# IDC-RJ45_connector_v1.net
KiCad netlist of a schematic drawn in EAGLE
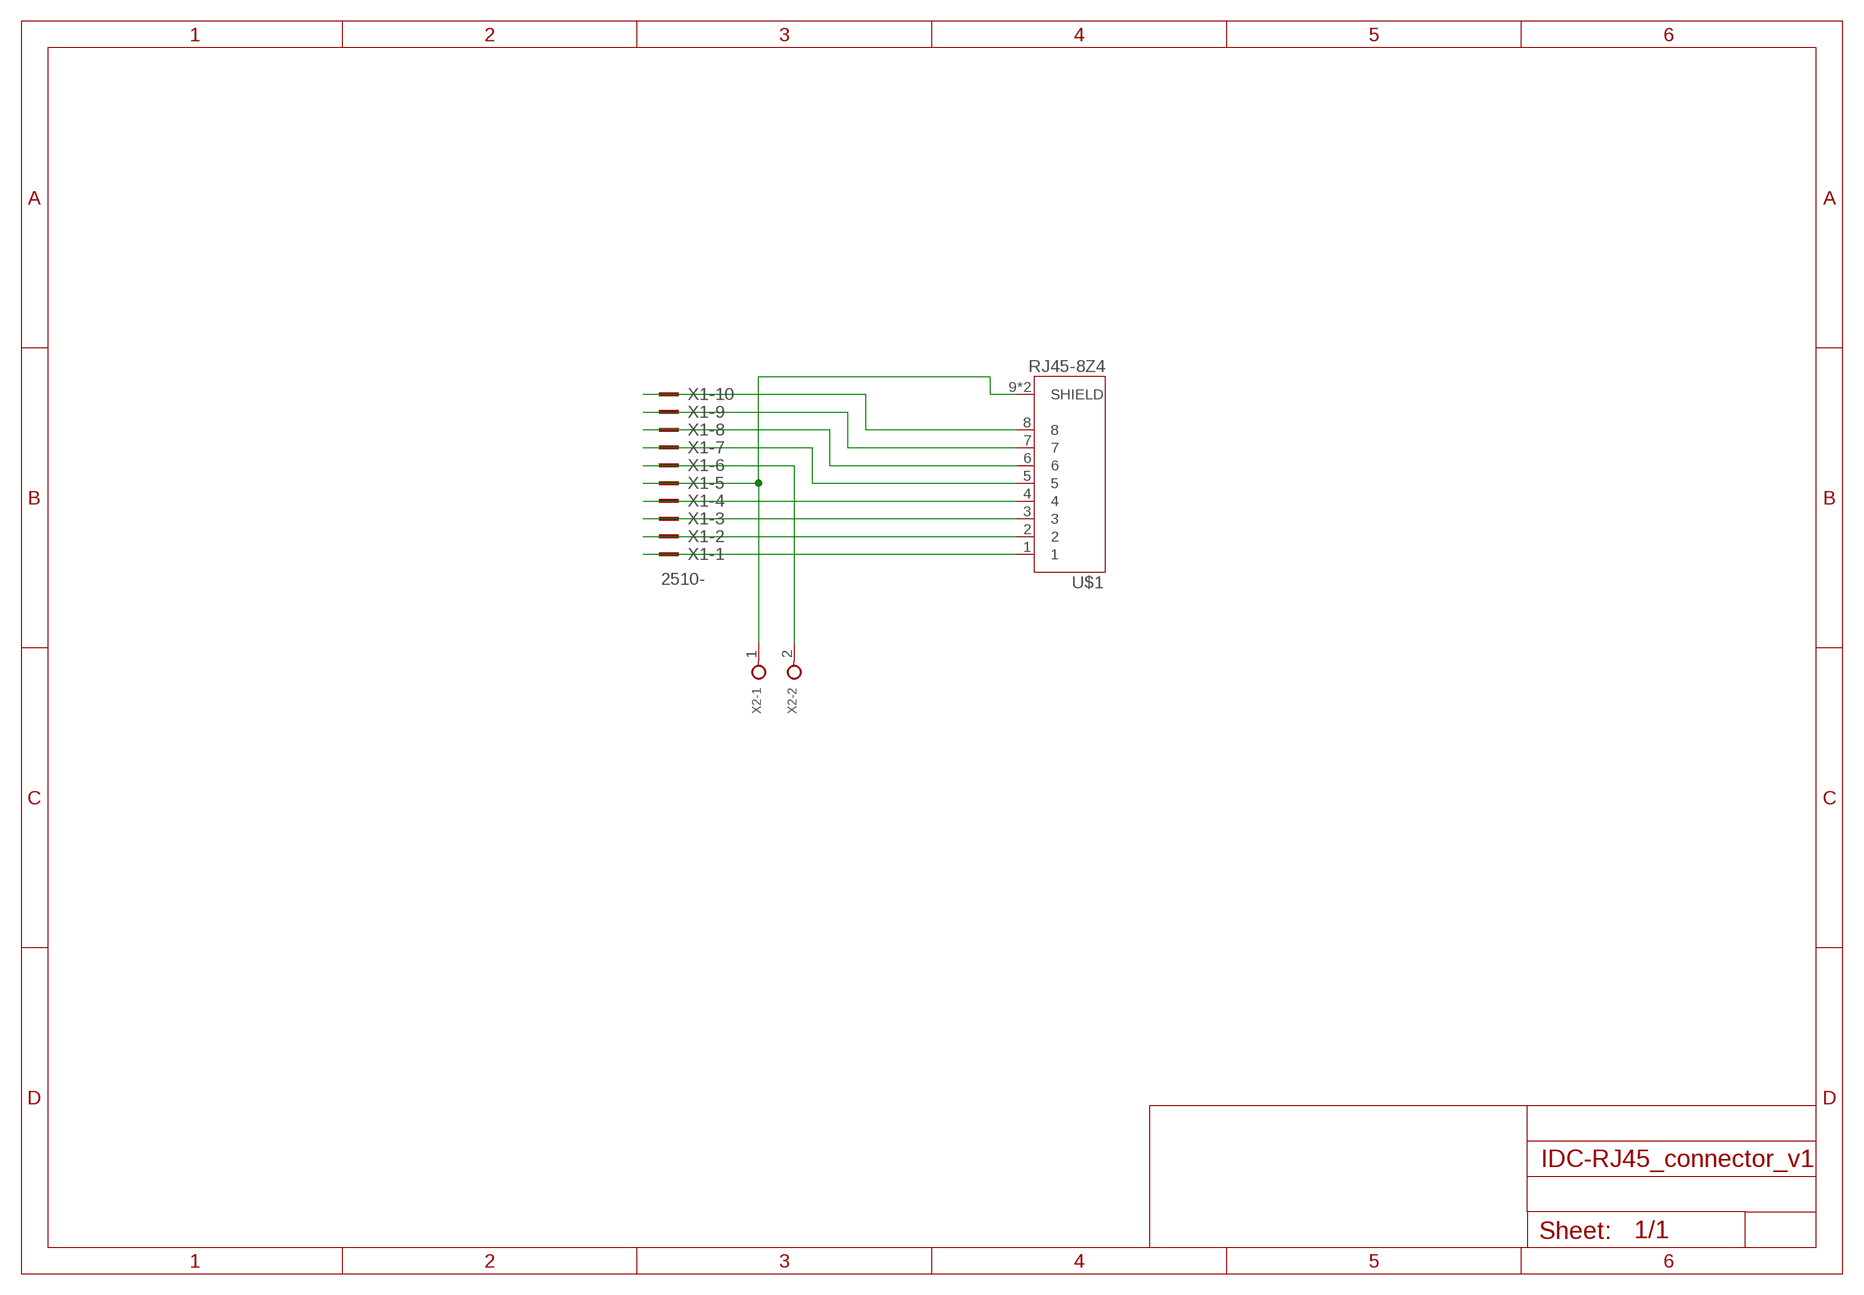
[diagram p0: schematic, sheet 1]

(export (version "E")
  (design (tool "Eeschema 10.0.6"))
  (components
    (comp (ref "U$1")
      (value "RJ45-8Z4")
      (footprint "eagle-import:TE_RJ45-8Z4")
      (fields (field (name "MF") "TE Connectivity"))
      (libsource (lib "eagle-import") (part "RJ45-8Z4"))
    )
    (comp (ref "X1")
      (value "2510-")
      (footprint "eagle-import:PAK100_2500-10")
      (fields (field (name "MF") "3M") (field (name "MPN") "2510-6002UB"))
      (libsource (lib "eagle-import") (part "2510-"))
    )
    (comp (ref "X2")
      (value "TERMINAL-5MM-2POLE")
      (footprint "eagle-import:TERMINAL_2P_5MM")
      (libsource (lib "eagle-import") (part "TERMINAL-5MM-2POLE"))
    )
  )
  (nets
    (net (code "1") (name "Net-(X1A-KL)") (class "Default")
      (node (ref "U$1") (pin "1") (pinfunction "1_1") (pintype "passive"))
      (node (ref "X1") (pin "1") (pinfunction "KL_1") (pintype "passive"))
    )
    (net (code "2") (name "Net-(X1B-KL)") (class "Default")
      (node (ref "U$1") (pin "8") (pinfunction "8_8") (pintype "passive"))
      (node (ref "X1") (pin "10") (pinfunction "KL_10") (pintype "passive"))
    )
    (net (code "3") (name "Net-(X1C-KL)") (class "Default")
      (node (ref "U$1") (pin "2") (pinfunction "2_2") (pintype "passive"))
      (node (ref "X1") (pin "2") (pinfunction "KL_2") (pintype "passive"))
    )
    (net (code "4") (name "Net-(X1D-KL)") (class "Default")
      (node (ref "U$1") (pin "3") (pinfunction "3_3") (pintype "passive"))
      (node (ref "X1") (pin "3") (pinfunction "KL_3") (pintype "passive"))
    )
    (net (code "5") (name "Net-(X1E-KL)") (class "Default")
      (node (ref "U$1") (pin "4") (pinfunction "4_4") (pintype "passive"))
      (node (ref "X1") (pin "4") (pinfunction "KL_4") (pintype "passive"))
    )
    (net (code "6") (name "Net-(X1F-KL)") (class "Default")
      (node (ref "U$1") (pin "10") (pinfunction "SHIELD_10") (pintype "passive"))
      (node (ref "U$1") (pin "9") (pinfunction "SHIELD_9") (pintype "passive"))
      (node (ref "X1") (pin "5") (pinfunction "KL_5") (pintype "passive"))
      (node (ref "X2") (pin "1") (pinfunction "P$1_1") (pintype "passive"))
    )
    (net (code "7") (name "Net-(X1G-KL)") (class "Default")
      (node (ref "X1") (pin "6") (pinfunction "KL_6") (pintype "passive"))
      (node (ref "X2") (pin "2") (pinfunction "P$2_2") (pintype "passive"))
    )
    (net (code "8") (name "Net-(X1H-KL)") (class "Default")
      (node (ref "U$1") (pin "5") (pinfunction "5_5") (pintype "passive"))
      (node (ref "X1") (pin "7") (pinfunction "KL_7") (pintype "passive"))
    )
    (net (code "9") (name "Net-(X1I-KL)") (class "Default")
      (node (ref "U$1") (pin "6") (pinfunction "6_6") (pintype "passive"))
      (node (ref "X1") (pin "8") (pinfunction "KL_8") (pintype "passive"))
    )
    (net (code "10") (name "Net-(X1J-KL)") (class "Default")
      (node (ref "U$1") (pin "7") (pinfunction "7_7") (pintype "passive"))
      (node (ref "X1") (pin "9") (pinfunction "KL_9") (pintype "passive"))
    )
  )
)
